# nixie_main_controller_board_0_2_2.net
KiCad netlist of a schematic drawn in EAGLE
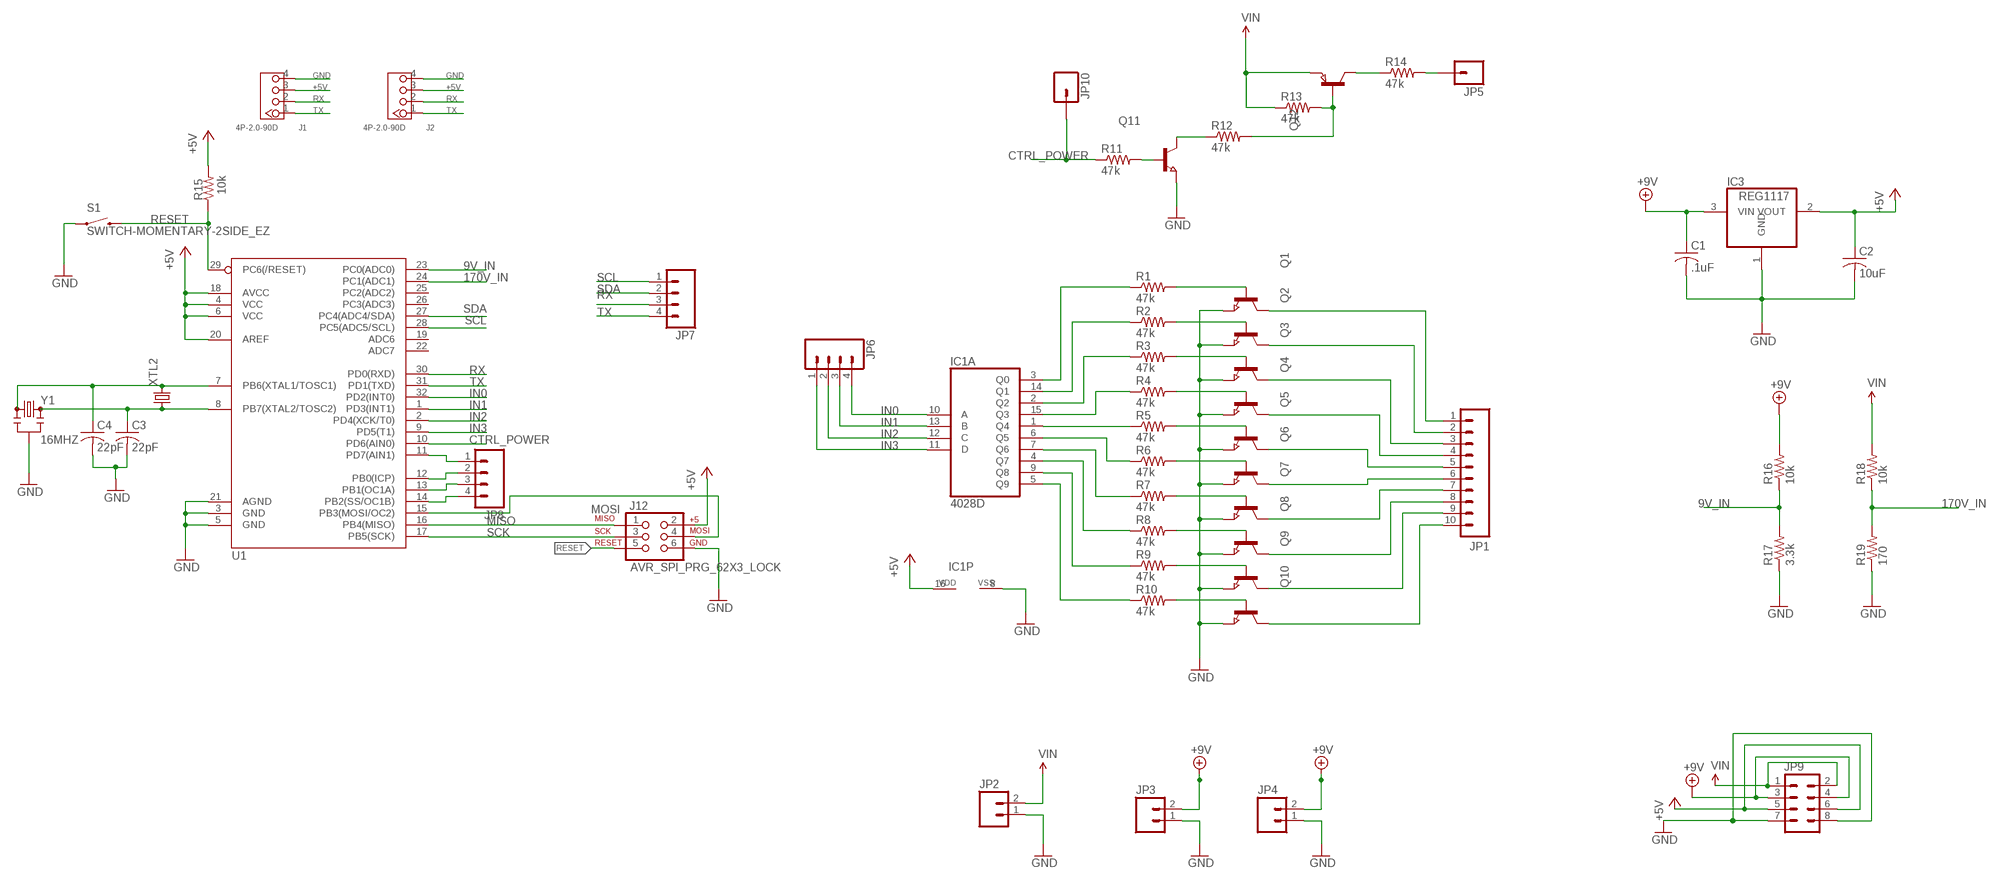
[diagram p0: schematic, sheet 1]

(export (version "E")
  (design (tool "Eeschema 10.0.6"))
  (components
    (comp (ref "C1")
      (value ".1uF")
      (footprint "eagle-import:C0603")
      (libsource (lib "eagle-import") (part "C-USC0603"))
    )
    (comp (ref "C2")
      (value "10uF")
      (footprint "eagle-import:C0805")
      (libsource (lib "eagle-import") (part "C-USC0805"))
    )
    (comp (ref "C3")
      (value "22pF")
      (footprint "eagle-import:C0603")
      (libsource (lib "eagle-import") (part "C-USC0603"))
    )
    (comp (ref "C4")
      (value "22pF")
      (footprint "eagle-import:C0603")
      (libsource (lib "eagle-import") (part "C-USC0603"))
    )
    (comp (ref "IC1")
      (value "4028D")
      (footprint "eagle-import:SO16")
      (libsource (lib "eagle-import") (part "4028D"))
    )
    (comp (ref "IC3")
      (value "REG1117")
      (footprint "eagle-import:SOT223")
      (libsource (lib "eagle-import") (part "REG1117"))
    )
    (comp (ref "J1")
      (value "4P-2.0-90D")
      (footprint "eagle-import:HW4-2.0-90D")
      (libsource (lib "eagle-import") (part "GROVE-CONNECTOR-DIP-90D(4P-2.0)"))
    )
    (comp (ref "J2")
      (value "4P-2.0-90D")
      (footprint "eagle-import:HW4-2.0-90D")
      (libsource (lib "eagle-import") (part "GROVE-CONNECTOR-DIP-90D(4P-2.0)"))
    )
    (comp (ref "J12")
      (value "AVR_SPI_PRG_62X3_LOCK")
      (footprint "eagle-import:2X3_LOCK")
      (libsource (lib "eagle-import") (part "AVR_SPI_PRG_62X3_LOCK"))
    )
    (comp (ref "JP1")
      (value "M10LOCK")
      (footprint "eagle-import:1X10_LOCK")
      (libsource (lib "eagle-import") (part "M10LOCK"))
    )
    (comp (ref "JP2")
      (value "M02LOCK")
      (footprint "eagle-import:1X02_LOCK")
      (libsource (lib "eagle-import") (part "M02LOCK"))
    )
    (comp (ref "JP3")
      (value "M02LOCK")
      (footprint "eagle-import:1X02_LOCK")
      (libsource (lib "eagle-import") (part "M02LOCK"))
    )
    (comp (ref "JP4")
      (value "M02LOCK")
      (footprint "eagle-import:1X02_LOCK")
      (libsource (lib "eagle-import") (part "M02LOCK"))
    )
    (comp (ref "JP5")
      (value "M01PTH")
      (footprint "eagle-import:1X01")
      (libsource (lib "eagle-import") (part "M01PTH"))
    )
    (comp (ref "JP6")
      (value "M04PTH")
      (footprint "eagle-import:1X04")
      (libsource (lib "eagle-import") (part "M04PTH"))
    )
    (comp (ref "JP7")
      (value "M04PTH")
      (footprint "eagle-import:1X04")
      (libsource (lib "eagle-import") (part "M04PTH"))
    )
    (comp (ref "JP8")
      (value "M04PTH")
      (footprint "eagle-import:1X04")
      (libsource (lib "eagle-import") (part "M04PTH"))
    )
    (comp (ref "JP9")
      (value "M04X2")
      (footprint "eagle-import:2X4")
      (libsource (lib "eagle-import") (part "M04X2"))
    )
    (comp (ref "JP10")
      (value "M01PTH")
      (footprint "eagle-import:1X01")
      (libsource (lib "eagle-import") (part "M01PTH"))
    )
    (comp (ref "Q1")
      (value "NPN-TRANSISTOR_SOT23")
      (footprint "eagle-import:SOT23")
      (libsource (lib "eagle-import") (part "NPN-TRANSISTOR_SOT23"))
    )
    (comp (ref "Q2")
      (value "NPN-TRANSISTOR_SOT23")
      (footprint "eagle-import:SOT23")
      (libsource (lib "eagle-import") (part "NPN-TRANSISTOR_SOT23"))
    )
    (comp (ref "Q3")
      (value "NPN-TRANSISTOR_SOT23")
      (footprint "eagle-import:SOT23")
      (libsource (lib "eagle-import") (part "NPN-TRANSISTOR_SOT23"))
    )
    (comp (ref "Q4")
      (value "NPN-TRANSISTOR_SOT23")
      (footprint "eagle-import:SOT23")
      (libsource (lib "eagle-import") (part "NPN-TRANSISTOR_SOT23"))
    )
    (comp (ref "Q5")
      (value "NPN-TRANSISTOR_SOT23")
      (footprint "eagle-import:SOT23")
      (libsource (lib "eagle-import") (part "NPN-TRANSISTOR_SOT23"))
    )
    (comp (ref "Q6")
      (value "NPN-TRANSISTOR_SOT23")
      (footprint "eagle-import:SOT23")
      (libsource (lib "eagle-import") (part "NPN-TRANSISTOR_SOT23"))
    )
    (comp (ref "Q7")
      (value "NPN-TRANSISTOR_SOT23")
      (footprint "eagle-import:SOT23")
      (libsource (lib "eagle-import") (part "NPN-TRANSISTOR_SOT23"))
    )
    (comp (ref "Q8")
      (value "NPN-TRANSISTOR_SOT23")
      (footprint "eagle-import:SOT23")
      (libsource (lib "eagle-import") (part "NPN-TRANSISTOR_SOT23"))
    )
    (comp (ref "Q9")
      (value "NPN-TRANSISTOR_SOT23")
      (footprint "eagle-import:SOT23")
      (libsource (lib "eagle-import") (part "NPN-TRANSISTOR_SOT23"))
    )
    (comp (ref "Q10")
      (value "NPN-TRANSISTOR_SOT23")
      (footprint "eagle-import:SOT23")
      (libsource (lib "eagle-import") (part "NPN-TRANSISTOR_SOT23"))
    )
    (comp (ref "Q11")
      (value "NPN-TRANSISTOR_SOT23")
      (footprint "eagle-import:SOT23")
      (libsource (lib "eagle-import") (part "NPN-TRANSISTOR_SOT23"))
    )
    (comp (ref "Q12")
      (value "PNP-TRANSISTOR_SOT23")
      (footprint "eagle-import:SOT23")
      (libsource (lib "eagle-import") (part "PNP-TRANSISTOR_SOT23"))
    )
    (comp (ref "R1")
      (value "47k")
      (footprint "eagle-import:R0603")
      (libsource (lib "eagle-import") (part "rcl_R-US_R0603"))
    )
    (comp (ref "R2")
      (value "47k")
      (footprint "eagle-import:R0603")
      (libsource (lib "eagle-import") (part "rcl_R-US_R0603"))
    )
    (comp (ref "R3")
      (value "47k")
      (footprint "eagle-import:R0603")
      (libsource (lib "eagle-import") (part "rcl_R-US_R0603"))
    )
    (comp (ref "R4")
      (value "47k")
      (footprint "eagle-import:R0603")
      (libsource (lib "eagle-import") (part "rcl_R-US_R0603"))
    )
    (comp (ref "R5")
      (value "47k")
      (footprint "eagle-import:R0603")
      (libsource (lib "eagle-import") (part "rcl_R-US_R0603"))
    )
    (comp (ref "R6")
      (value "47k")
      (footprint "eagle-import:R0603")
      (libsource (lib "eagle-import") (part "rcl_R-US_R0603"))
    )
    (comp (ref "R7")
      (value "47k")
      (footprint "eagle-import:R0603")
      (libsource (lib "eagle-import") (part "rcl_R-US_R0603"))
    )
    (comp (ref "R8")
      (value "47k")
      (footprint "eagle-import:R0603")
      (libsource (lib "eagle-import") (part "rcl_R-US_R0603"))
    )
    (comp (ref "R9")
      (value "47k")
      (footprint "eagle-import:R0603")
      (libsource (lib "eagle-import") (part "rcl_R-US_R0603"))
    )
    (comp (ref "R10")
      (value "47k")
      (footprint "eagle-import:R0603")
      (libsource (lib "eagle-import") (part "rcl_R-US_R0603"))
    )
    (comp (ref "R11")
      (value "47k")
      (footprint "eagle-import:R0603")
      (libsource (lib "eagle-import") (part "rcl_R-US_R0603"))
    )
    (comp (ref "R12")
      (value "47k")
      (footprint "eagle-import:R0603")
      (libsource (lib "eagle-import") (part "rcl_R-US_R0603"))
    )
    (comp (ref "R13")
      (value "47k")
      (footprint "eagle-import:R0603")
      (libsource (lib "eagle-import") (part "rcl_R-US_R0603"))
    )
    (comp (ref "R14")
      (value "47k")
      (footprint "eagle-import:R0603")
      (libsource (lib "eagle-import") (part "rcl_R-US_R0603"))
    )
    (comp (ref "R15")
      (value "10k")
      (footprint "eagle-import:0603")
      (libsource (lib "eagle-import") (part "RESISTOR0603-RES"))
    )
    (comp (ref "R16")
      (value "10k")
      (footprint "eagle-import:R0603")
      (libsource (lib "eagle-import") (part "rcl_R-US_R0603"))
    )
    (comp (ref "R17")
      (value "3.3k")
      (footprint "eagle-import:R0603")
      (libsource (lib "eagle-import") (part "rcl_R-US_R0603"))
    )
    (comp (ref "R18")
      (value "10k")
      (footprint "eagle-import:R0603")
      (libsource (lib "eagle-import") (part "rcl_R-US_R0603"))
    )
    (comp (ref "R19")
      (value "170")
      (footprint "eagle-import:M1206")
      (libsource (lib "eagle-import") (part "R-US_M1206"))
    )
    (comp (ref "S1")
      (value "SWITCH-MOMENTARY-2SIDE_EZ")
      (footprint "eagle-import:TACTILE-PTH-SIDEEZ")
      (libsource (lib "eagle-import") (part "SWITCH-MOMENTARY-2SIDE_EZ"))
    )
    (comp (ref "U1")
      (value "ATMEGA328_SMT")
      (footprint "eagle-import:TQFP32-08")
      (libsource (lib "eagle-import") (part "ATMEGA328_SMT"))
    )
    (comp (ref "XTL2")
      (value "CRYSTALHC49S")
      (footprint "eagle-import:HC49_S")
      (libsource (lib "eagle-import") (part "CRYSTALHC49S"))
    )
    (comp (ref "Y1")
      (value "16MHZ")
      (footprint "eagle-import:RESONATOR-SMD")
      (libsource (lib "eagle-import") (part "RESONATOR16MHZ"))
    )
  )
  (nets
    (net (code "1") (name "+5V") (class "Default")
      (node (ref "C2") (pin "1") (pinfunction "1_1") (pintype "passive"))
      (node (ref "IC1") (pin "16") (pinfunction "VDD_16") (pintype "power_in"))
      (node (ref "IC3") (pin "2") (pinfunction "VOUT_2") (pintype "output"))
      (node (ref "J1") (pin "3") (pinfunction "3_3") (pintype "bidirectional"))
      (node (ref "J12") (pin "2") (pinfunction "2_2") (pintype "passive"))
      (node (ref "J2") (pin "3") (pinfunction "3_3") (pintype "bidirectional"))
      (node (ref "JP9") (pin "5") (pinfunction "5_5") (pintype "passive"))
      (node (ref "JP9") (pin "6") (pinfunction "6_6") (pintype "passive"))
      (node (ref "R15") (pin "2") (pinfunction "2_2") (pintype "passive"))
      (node (ref "U1") (pin "18") (pinfunction "AVCC_18") (pintype "bidirectional"))
      (node (ref "U1") (pin "20") (pinfunction "AREF_20") (pintype "bidirectional"))
      (node (ref "U1") (pin "4") (pinfunction "VCC_4") (pintype "bidirectional"))
      (node (ref "U1") (pin "6") (pinfunction "VCC_6") (pintype "bidirectional"))
    )
    (net (code "2") (name "+9V") (class "Default")
      (node (ref "C1") (pin "1") (pinfunction "1_1") (pintype "passive"))
      (node (ref "IC3") (pin "3") (pinfunction "VIN_3") (pintype "input"))
      (node (ref "JP3") (pin "2") (pinfunction "2_2") (pintype "passive"))
      (node (ref "JP4") (pin "2") (pinfunction "2_2") (pintype "passive"))
      (node (ref "JP9") (pin "3") (pinfunction "3_3") (pintype "passive"))
      (node (ref "JP9") (pin "4") (pinfunction "4_4") (pintype "passive"))
      (node (ref "R16") (pin "2") (pinfunction "2_2") (pintype "passive"))
    )
    (net (code "3") (name "/9V_IN") (class "Default")
      (node (ref "R16") (pin "1") (pinfunction "1_1") (pintype "passive"))
      (node (ref "R17") (pin "2") (pinfunction "2_2") (pintype "passive"))
      (node (ref "U1") (pin "23") (pinfunction "PC0(ADC0)_23") (pintype "bidirectional"))
    )
    (net (code "4") (name "/170V_IN") (class "Default")
      (node (ref "R18") (pin "1") (pinfunction "1_1") (pintype "passive"))
      (node (ref "R19") (pin "2") (pinfunction "2_2") (pintype "passive"))
      (node (ref "U1") (pin "24") (pinfunction "PC1(ADC1)_24") (pintype "bidirectional"))
    )
    (net (code "5") (name "/CTRL_POWER") (class "Default")
      (node (ref "JP10") (pin "1") (pinfunction "1_1") (pintype "passive"))
      (node (ref "R11") (pin "1") (pinfunction "1_1") (pintype "passive"))
      (node (ref "U1") (pin "10") (pinfunction "PD6(AIN0)_10") (pintype "bidirectional"))
    )
    (net (code "6") (name "/IN0") (class "Default")
      (node (ref "IC1") (pin "10") (pinfunction "A_10") (pintype "input"))
      (node (ref "JP6") (pin "4") (pinfunction "4_4") (pintype "passive"))
      (node (ref "U1") (pin "32") (pinfunction "PD2(INT0)_32") (pintype "bidirectional"))
    )
    (net (code "7") (name "/IN1") (class "Default")
      (node (ref "IC1") (pin "13") (pinfunction "B_13") (pintype "input"))
      (node (ref "JP6") (pin "3") (pinfunction "3_3") (pintype "passive"))
      (node (ref "U1") (pin "1") (pinfunction "PD3(INT1)_1") (pintype "bidirectional"))
    )
    (net (code "8") (name "/IN2") (class "Default")
      (node (ref "IC1") (pin "12") (pinfunction "C_12") (pintype "input"))
      (node (ref "JP6") (pin "2") (pinfunction "2_2") (pintype "passive"))
      (node (ref "U1") (pin "2") (pinfunction "PD4(XCK/T0)_2") (pintype "bidirectional"))
    )
    (net (code "9") (name "/IN3") (class "Default")
      (node (ref "IC1") (pin "11") (pinfunction "D_11") (pintype "input"))
      (node (ref "JP6") (pin "1") (pinfunction "1_1") (pintype "passive"))
      (node (ref "U1") (pin "9") (pinfunction "PD5(T1)_9") (pintype "bidirectional"))
    )
    (net (code "10") (name "/MISO") (class "Default")
      (node (ref "J12") (pin "1") (pinfunction "1_1") (pintype "passive"))
      (node (ref "U1") (pin "16") (pinfunction "PB4(MISO)_16") (pintype "bidirectional"))
    )
    (net (code "11") (name "/MOSI") (class "Default")
      (node (ref "J12") (pin "4") (pinfunction "4_4") (pintype "passive"))
      (node (ref "U1") (pin "15") (pinfunction "PB3(MOSI/OC2)_15") (pintype "bidirectional"))
    )
    (net (code "12") (name "/RX") (class "Default")
      (node (ref "J1") (pin "2") (pinfunction "2_2") (pintype "bidirectional"))
      (node (ref "J2") (pin "2") (pinfunction "2_2") (pintype "bidirectional"))
      (node (ref "JP7") (pin "3") (pinfunction "3_3") (pintype "passive"))
      (node (ref "U1") (pin "30") (pinfunction "PD0(RXD)_30") (pintype "bidirectional"))
    )
    (net (code "13") (name "/SCK") (class "Default")
      (node (ref "J12") (pin "3") (pinfunction "3_3") (pintype "passive"))
      (node (ref "U1") (pin "17") (pinfunction "PB5(SCK)_17") (pintype "bidirectional"))
    )
    (net (code "14") (name "/SCL") (class "Default")
      (node (ref "JP7") (pin "1") (pinfunction "1_1") (pintype "passive"))
      (node (ref "U1") (pin "28") (pinfunction "PC5(ADC5/SCL)_28") (pintype "bidirectional"))
    )
    (net (code "15") (name "/SDA") (class "Default")
      (node (ref "JP7") (pin "2") (pinfunction "2_2") (pintype "passive"))
      (node (ref "U1") (pin "27") (pinfunction "PC4(ADC4/SDA)_27") (pintype "bidirectional"))
    )
    (net (code "16") (name "/TX") (class "Default")
      (node (ref "J1") (pin "1") (pinfunction "1_1") (pintype "bidirectional"))
      (node (ref "J2") (pin "1") (pinfunction "1_1") (pintype "bidirectional"))
      (node (ref "JP7") (pin "4") (pinfunction "4_4") (pintype "passive"))
      (node (ref "U1") (pin "31") (pinfunction "PD1(TXD)_31") (pintype "bidirectional"))
    )
    (net (code "17") (name "GND") (class "Default")
      (node (ref "C1") (pin "2") (pinfunction "2_2") (pintype "passive"))
      (node (ref "C2") (pin "2") (pinfunction "2_2") (pintype "passive"))
      (node (ref "C3") (pin "2") (pinfunction "2_2") (pintype "passive"))
      (node (ref "C4") (pin "2") (pinfunction "2_2") (pintype "passive"))
      (node (ref "IC1") (pin "8") (pinfunction "VSS_8") (pintype "power_in"))
      (node (ref "IC3") (pin "1") (pinfunction "GND_1") (pintype "power_in"))
      (node (ref "J1") (pin "4") (pinfunction "4_4") (pintype "bidirectional"))
      (node (ref "J12") (pin "6") (pinfunction "6_6") (pintype "passive"))
      (node (ref "J2") (pin "4") (pinfunction "4_4") (pintype "bidirectional"))
      (node (ref "JP2") (pin "1") (pinfunction "1_1") (pintype "passive"))
      (node (ref "JP3") (pin "1") (pinfunction "1_1") (pintype "passive"))
      (node (ref "JP4") (pin "1") (pinfunction "1_1") (pintype "passive"))
      (node (ref "JP9") (pin "7") (pinfunction "7_7") (pintype "passive"))
      (node (ref "JP9") (pin "8") (pinfunction "8_8") (pintype "passive"))
      (node (ref "Q1") (pin "2") (pinfunction "E_2") (pintype "passive"))
      (node (ref "Q10") (pin "2") (pinfunction "E_2") (pintype "passive"))
      (node (ref "Q11") (pin "2") (pinfunction "E_2") (pintype "passive"))
      (node (ref "Q2") (pin "2") (pinfunction "E_2") (pintype "passive"))
      (node (ref "Q3") (pin "2") (pinfunction "E_2") (pintype "passive"))
      (node (ref "Q4") (pin "2") (pinfunction "E_2") (pintype "passive"))
      (node (ref "Q5") (pin "2") (pinfunction "E_2") (pintype "passive"))
      (node (ref "Q6") (pin "2") (pinfunction "E_2") (pintype "passive"))
      (node (ref "Q7") (pin "2") (pinfunction "E_2") (pintype "passive"))
      (node (ref "Q8") (pin "2") (pinfunction "E_2") (pintype "passive"))
      (node (ref "Q9") (pin "2") (pinfunction "E_2") (pintype "passive"))
      (node (ref "R17") (pin "1") (pinfunction "1_1") (pintype "passive"))
      (node (ref "R19") (pin "1") (pinfunction "1_1") (pintype "passive"))
      (node (ref "S1") (pin "1") (pinfunction "1_1") (pintype "passive"))
      (node (ref "U1") (pin "21") (pinfunction "AGND_21") (pintype "bidirectional"))
      (node (ref "U1") (pin "3") (pinfunction "GND_3") (pintype "bidirectional"))
      (node (ref "U1") (pin "5") (pinfunction "GND_5") (pintype "bidirectional"))
      (node (ref "Y1") (pin "2") (pinfunction "2_2") (pintype "passive"))
    )
    (net (code "18") (name "Net-(IC1A-Q0)") (class "Default")
      (node (ref "IC1") (pin "3") (pinfunction "Q0_3") (pintype "output"))
      (node (ref "R1") (pin "1") (pinfunction "1_1") (pintype "passive"))
    )
    (net (code "19") (name "Net-(IC1A-Q1)") (class "Default")
      (node (ref "IC1") (pin "14") (pinfunction "Q1_14") (pintype "output"))
      (node (ref "R2") (pin "1") (pinfunction "1_1") (pintype "passive"))
    )
    (net (code "20") (name "Net-(IC1A-Q2)") (class "Default")
      (node (ref "IC1") (pin "2") (pinfunction "Q2_2") (pintype "output"))
      (node (ref "R3") (pin "1") (pinfunction "1_1") (pintype "passive"))
    )
    (net (code "21") (name "Net-(IC1A-Q3)") (class "Default")
      (node (ref "IC1") (pin "15") (pinfunction "Q3_15") (pintype "output"))
      (node (ref "R4") (pin "1") (pinfunction "1_1") (pintype "passive"))
    )
    (net (code "22") (name "Net-(IC1A-Q4)") (class "Default")
      (node (ref "IC1") (pin "1") (pinfunction "Q4_1") (pintype "output"))
      (node (ref "R5") (pin "1") (pinfunction "1_1") (pintype "passive"))
    )
    (net (code "23") (name "Net-(IC1A-Q5)") (class "Default")
      (node (ref "IC1") (pin "6") (pinfunction "Q5_6") (pintype "output"))
      (node (ref "R6") (pin "1") (pinfunction "1_1") (pintype "passive"))
    )
    (net (code "24") (name "Net-(IC1A-Q6)") (class "Default")
      (node (ref "IC1") (pin "7") (pinfunction "Q6_7") (pintype "output"))
      (node (ref "R7") (pin "1") (pinfunction "1_1") (pintype "passive"))
    )
    (net (code "25") (name "Net-(IC1A-Q7)") (class "Default")
      (node (ref "IC1") (pin "4") (pinfunction "Q7_4") (pintype "output"))
      (node (ref "R8") (pin "1") (pinfunction "1_1") (pintype "passive"))
    )
    (net (code "26") (name "Net-(IC1A-Q8)") (class "Default")
      (node (ref "IC1") (pin "9") (pinfunction "Q8_9") (pintype "output"))
      (node (ref "R9") (pin "1") (pinfunction "1_1") (pintype "passive"))
    )
    (net (code "27") (name "Net-(IC1A-Q9)") (class "Default")
      (node (ref "IC1") (pin "5") (pinfunction "Q9_5") (pintype "output"))
      (node (ref "R10") (pin "1") (pinfunction "1_1") (pintype "passive"))
    )
    (net (code "28") (name "Net-(JP5-Pad1)") (class "Default")
      (node (ref "JP5") (pin "1") (pinfunction "1_1") (pintype "passive"))
      (node (ref "R14") (pin "2") (pinfunction "2_2") (pintype "passive"))
    )
    (net (code "29") (name "Net-(Q1-B)") (class "Default")
      (node (ref "Q1") (pin "1") (pinfunction "B_1") (pintype "passive"))
      (node (ref "R1") (pin "2") (pinfunction "2_2") (pintype "passive"))
    )
    (net (code "30") (name "Net-(Q1-C)") (class "Default")
      (node (ref "JP1") (pin "1") (pinfunction "1_1") (pintype "passive"))
      (node (ref "Q1") (pin "3") (pinfunction "C_3") (pintype "passive"))
    )
    (net (code "31") (name "Net-(Q2-B)") (class "Default")
      (node (ref "Q2") (pin "1") (pinfunction "B_1") (pintype "passive"))
      (node (ref "R2") (pin "2") (pinfunction "2_2") (pintype "passive"))
    )
    (net (code "32") (name "Net-(Q2-C)") (class "Default")
      (node (ref "JP1") (pin "2") (pinfunction "2_2") (pintype "passive"))
      (node (ref "Q2") (pin "3") (pinfunction "C_3") (pintype "passive"))
    )
    (net (code "33") (name "Net-(Q3-B)") (class "Default")
      (node (ref "Q3") (pin "1") (pinfunction "B_1") (pintype "passive"))
      (node (ref "R3") (pin "2") (pinfunction "2_2") (pintype "passive"))
    )
    (net (code "34") (name "Net-(Q3-C)") (class "Default")
      (node (ref "JP1") (pin "3") (pinfunction "3_3") (pintype "passive"))
      (node (ref "Q3") (pin "3") (pinfunction "C_3") (pintype "passive"))
    )
    (net (code "35") (name "Net-(Q4-B)") (class "Default")
      (node (ref "Q4") (pin "1") (pinfunction "B_1") (pintype "passive"))
      (node (ref "R4") (pin "2") (pinfunction "2_2") (pintype "passive"))
    )
    (net (code "36") (name "Net-(Q4-C)") (class "Default")
      (node (ref "JP1") (pin "4") (pinfunction "4_4") (pintype "passive"))
      (node (ref "Q4") (pin "3") (pinfunction "C_3") (pintype "passive"))
    )
    (net (code "37") (name "Net-(Q5-B)") (class "Default")
      (node (ref "Q5") (pin "1") (pinfunction "B_1") (pintype "passive"))
      (node (ref "R5") (pin "2") (pinfunction "2_2") (pintype "passive"))
    )
    (net (code "38") (name "Net-(Q5-C)") (class "Default")
      (node (ref "JP1") (pin "5") (pinfunction "5_5") (pintype "passive"))
      (node (ref "Q5") (pin "3") (pinfunction "C_3") (pintype "passive"))
    )
    (net (code "39") (name "Net-(Q6-B)") (class "Default")
      (node (ref "Q6") (pin "1") (pinfunction "B_1") (pintype "passive"))
      (node (ref "R6") (pin "2") (pinfunction "2_2") (pintype "passive"))
    )
    (net (code "40") (name "Net-(Q6-C)") (class "Default")
      (node (ref "JP1") (pin "6") (pinfunction "6_6") (pintype "passive"))
      (node (ref "Q6") (pin "3") (pinfunction "C_3") (pintype "passive"))
    )
    (net (code "41") (name "Net-(Q7-B)") (class "Default")
      (node (ref "Q7") (pin "1") (pinfunction "B_1") (pintype "passive"))
      (node (ref "R7") (pin "2") (pinfunction "2_2") (pintype "passive"))
    )
    (net (code "42") (name "Net-(Q7-C)") (class "Default")
      (node (ref "JP1") (pin "7") (pinfunction "7_7") (pintype "passive"))
      (node (ref "Q7") (pin "3") (pinfunction "C_3") (pintype "passive"))
    )
    (net (code "43") (name "Net-(Q8-B)") (class "Default")
      (node (ref "Q8") (pin "1") (pinfunction "B_1") (pintype "passive"))
      (node (ref "R8") (pin "2") (pinfunction "2_2") (pintype "passive"))
    )
    (net (code "44") (name "Net-(Q8-C)") (class "Default")
      (node (ref "JP1") (pin "8") (pinfunction "8_8") (pintype "passive"))
      (node (ref "Q8") (pin "3") (pinfunction "C_3") (pintype "passive"))
    )
    (net (code "45") (name "Net-(Q9-B)") (class "Default")
      (node (ref "Q9") (pin "1") (pinfunction "B_1") (pintype "passive"))
      (node (ref "R9") (pin "2") (pinfunction "2_2") (pintype "passive"))
    )
    (net (code "46") (name "Net-(Q9-C)") (class "Default")
      (node (ref "JP1") (pin "9") (pinfunction "9_9") (pintype "passive"))
      (node (ref "Q9") (pin "3") (pinfunction "C_3") (pintype "passive"))
    )
    (net (code "47") (name "Net-(Q10-B)") (class "Default")
      (node (ref "Q10") (pin "1") (pinfunction "B_1") (pintype "passive"))
      (node (ref "R10") (pin "2") (pinfunction "2_2") (pintype "passive"))
    )
    (net (code "48") (name "Net-(Q10-C)") (class "Default")
      (node (ref "JP1") (pin "10") (pinfunction "10_10") (pintype "passive"))
      (node (ref "Q10") (pin "3") (pinfunction "C_3") (pintype "passive"))
    )
    (net (code "49") (name "Net-(Q11-B)") (class "Default")
      (node (ref "Q11") (pin "1") (pinfunction "B_1") (pintype "passive"))
      (node (ref "R11") (pin "2") (pinfunction "2_2") (pintype "passive"))
    )
    (net (code "50") (name "Net-(Q11-C)") (class "Default")
      (node (ref "Q11") (pin "3") (pinfunction "C_3") (pintype "passive"))
      (node (ref "R12") (pin "1") (pinfunction "1_1") (pintype "passive"))
    )
    (net (code "51") (name "Net-(Q12-B)") (class "Default")
      (node (ref "Q12") (pin "1") (pinfunction "B_1") (pintype "passive"))
      (node (ref "R12") (pin "2") (pinfunction "2_2") (pintype "passive"))
      (node (ref "R13") (pin "2") (pinfunction "2_2") (pintype "passive"))
    )
    (net (code "52") (name "Net-(Q12-C)") (class "Default")
      (node (ref "Q12") (pin "3") (pinfunction "C_3") (pintype "passive"))
      (node (ref "R14") (pin "1") (pinfunction "1_1") (pintype "passive"))
    )
    (net (code "53") (name "Net-(U1-PB0(ICP))") (class "Default")
      (node (ref "JP8") (pin "2") (pinfunction "2_2") (pintype "passive"))
      (node (ref "U1") (pin "12") (pinfunction "PB0(ICP)_12") (pintype "bidirectional"))
    )
    (net (code "54") (name "Net-(U1-PB1(OC1A))") (class "Default")
      (node (ref "JP8") (pin "3") (pinfunction "3_3") (pintype "passive"))
      (node (ref "U1") (pin "13") (pinfunction "PB1(OC1A)_13") (pintype "bidirectional"))
    )
    (net (code "55") (name "Net-(U1-PB2(SS{slash}OC1B))") (class "Default")
      (node (ref "JP8") (pin "4") (pinfunction "4_4") (pintype "passive"))
      (node (ref "U1") (pin "14") (pinfunction "PB2(SS/OC1B)_14") (pintype "bidirectional"))
    )
    (net (code "56") (name "Net-(U1-PB6(XTAL1{slash}TOSC1))") (class "Default")
      (node (ref "C4") (pin "1") (pinfunction "1_1") (pintype "passive"))
      (node (ref "U1") (pin "7") (pinfunction "PB6(XTAL1/TOSC1)_7") (pintype "bidirectional"))
      (node (ref "XTL2") (pin "2") (pinfunction "2_2") (pintype "passive"))
      (node (ref "Y1") (pin "1") (pinfunction "1_1") (pintype "passive"))
    )
    (net (code "57") (name "Net-(U1-PB7(XTAL2{slash}TOSC2))") (class "Default")
      (node (ref "C3") (pin "1") (pinfunction "1_1") (pintype "passive"))
      (node (ref "U1") (pin "8") (pinfunction "PB7(XTAL2/TOSC2)_8") (pintype "bidirectional"))
      (node (ref "XTL2") (pin "1") (pinfunction "1_1") (pintype "passive"))
      (node (ref "Y1") (pin "3") (pinfunction "3_3") (pintype "passive"))
    )
    (net (code "58") (name "Net-(U1-PD7(AIN1))") (class "Default")
      (node (ref "JP8") (pin "1") (pinfunction "1_1") (pintype "passive"))
      (node (ref "U1") (pin "11") (pinfunction "PD7(AIN1)_11") (pintype "bidirectional"))
    )
    (net (code "59") (name "RESET") (class "Default")
      (node (ref "J12") (pin "5") (pinfunction "5_5") (pintype "passive"))
      (node (ref "R15") (pin "1") (pinfunction "1_1") (pintype "passive"))
      (node (ref "S1") (pin "2") (pinfunction "2_2") (pintype "passive"))
      (node (ref "U1") (pin "29") (pinfunction "PC6(/RESET)_29") (pintype "bidirectional"))
    )
    (net (code "60") (name "VIN") (class "Default")
      (node (ref "JP2") (pin "2") (pinfunction "2_2") (pintype "passive"))
      (node (ref "JP9") (pin "1") (pinfunction "1_1") (pintype "passive"))
      (node (ref "JP9") (pin "2") (pinfunction "2_2") (pintype "passive"))
      (node (ref "Q12") (pin "2") (pinfunction "E_2") (pintype "passive"))
      (node (ref "R13") (pin "1") (pinfunction "1_1") (pintype "passive"))
      (node (ref "R18") (pin "2") (pinfunction "2_2") (pintype "passive"))
    )
    (net (code "61") (name "unconnected-(U1-ADC6-Pad19)") (class "Default")
      (node (ref "U1") (pin "19") (pinfunction "ADC6_19") (pintype "bidirectional"))
    )
    (net (code "62") (name "unconnected-(U1-ADC7-Pad22)") (class "Default")
      (node (ref "U1") (pin "22") (pinfunction "ADC7_22") (pintype "bidirectional"))
    )
    (net (code "63") (name "unconnected-(U1-PC2(ADC2)-Pad25)") (class "Default")
      (node (ref "U1") (pin "25") (pinfunction "PC2(ADC2)_25") (pintype "bidirectional"))
    )
    (net (code "64") (name "unconnected-(U1-PC3(ADC3)-Pad26)") (class "Default")
      (node (ref "U1") (pin "26") (pinfunction "PC3(ADC3)_26") (pintype "bidirectional"))
    )
  )
)
